# Analog_Interfaces.net
KiCad netlist of a schematic drawn in Altium Designer
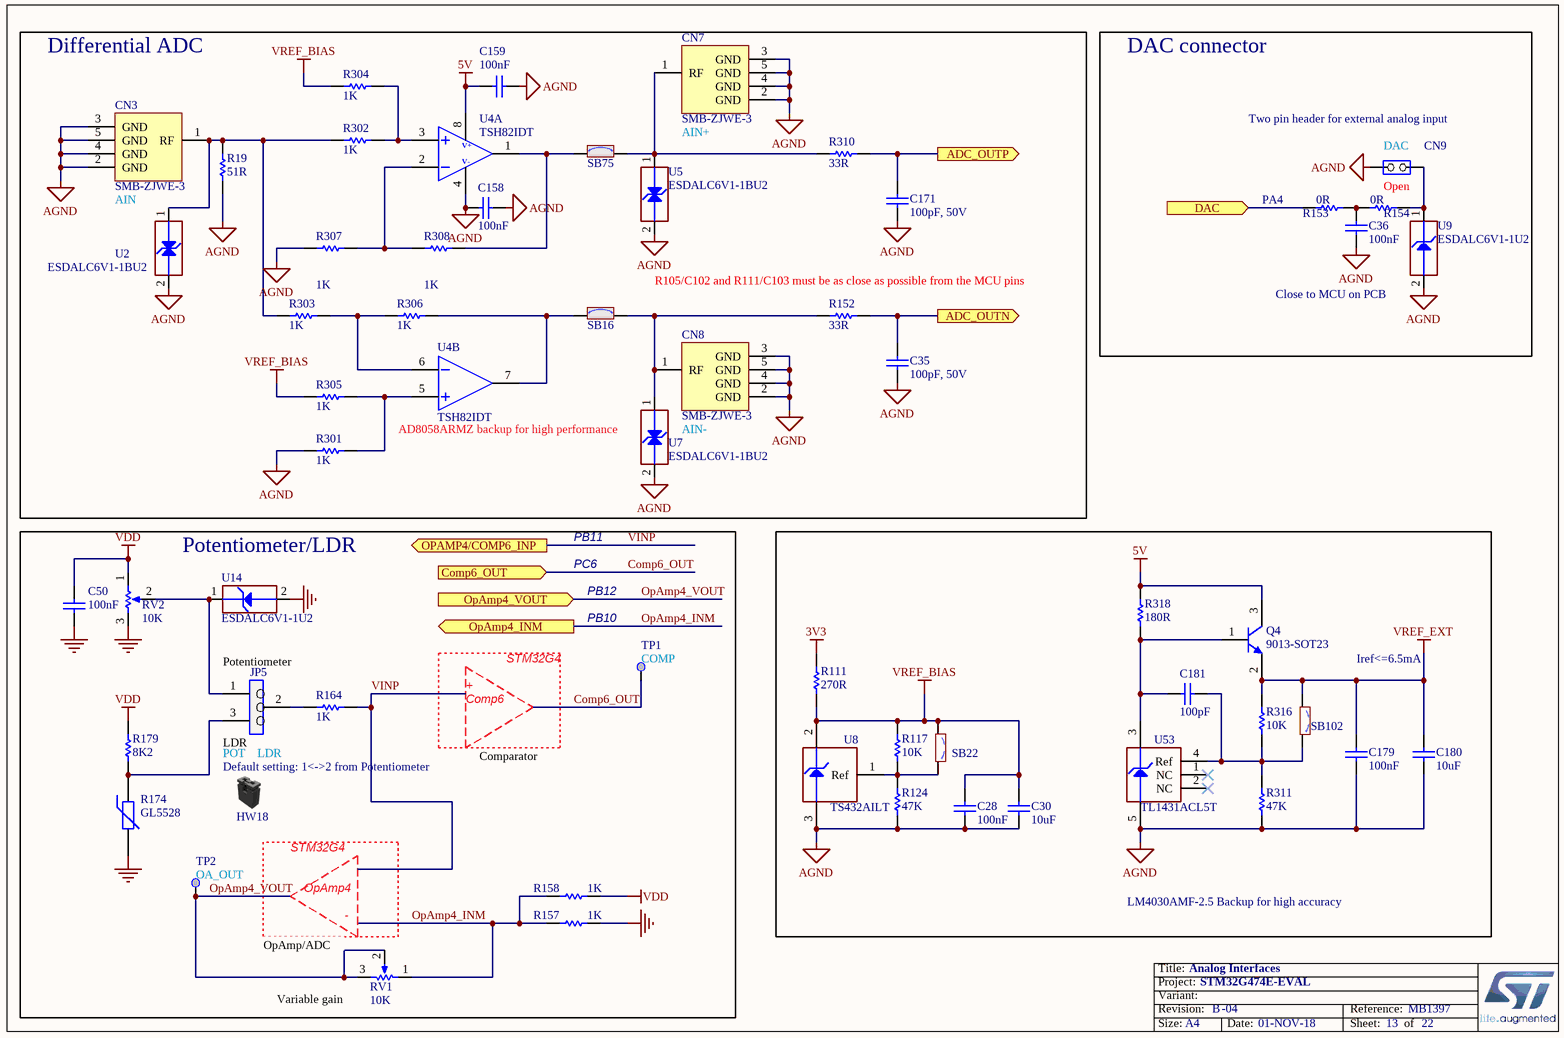
[diagram p0: Analog Interfaces.SchDoc]

(export (version "E")
  (design (tool "Eeschema 10.0.6"))
  (components
    (comp (ref "C28")
      (value "100nF")
      (footprint "C0603")
      (description "Capacitor, MLCC, 100nF, 16V, X7R, 10%, 0603, T=0,8mm")
      (fields
        (field (name "INTERNAL_PART_NUMBER") "MCD-00211")
        (field (name "MANUFACTURER_PART_NUMBER") "CC0603KRX7R7BB104")
        (field (name "PROVIDED_BY") "SUBCO")
      )
      (libsource (lib "MCD_PARTS_database") (part "Capacitor"))
    )
    (comp (ref "C30")
      (value "10uF")
      (footprint "C0603")
      (description "Capacitor, MLCC, 10µF, 10V, X5R, 10%, 0603, T=0.8mm")
      (fields
        (field (name "INTERNAL_PART_NUMBER") "MCD-01124")
        (field (name "MANUFACTURER_PART_NUMBER") "GRM188R61A106KAAL")
        (field (name "PROVIDED_BY") "SUBCO")
      )
      (libsource (lib "MCD_PARTS_database") (part "Capacitor"))
    )
    (comp (ref "C35")
      (value "100pF, 50V")
      (footprint "C0603")
      (description "Capacitor,100pF,50V,X7R,10%,0603")
      (fields
        (field (name "INTERNAL_PART_NUMBER") "MCD-01101")
        (field (name "MANUFACTURER_PART_NUMBER") "06035C101JAT4A")
        (field (name "PROVIDED_BY") "SUBCO")
      )
      (libsource (lib "MCD_PARTS_database") (part "Capacitor"))
    )
    (comp (ref "C36")
      (value "100nF")
      (footprint "C0603")
      (description "Capacitor, MLCC, 100nF, 16V, X7R, 10%, 0603, T=0,8mm")
      (fields
        (field (name "INTERNAL_PART_NUMBER") "MCD-00211")
        (field (name "MANUFACTURER_PART_NUMBER") "CC0603KRX7R7BB104")
        (field (name "PROVIDED_BY") "SUBCO")
      )
      (libsource (lib "MCD_PARTS_database") (part "Capacitor"))
    )
    (comp (ref "C50")
      (value "100nF")
      (footprint "C0402")
      (description "Capacitor, MLCC, 100nF, 16V, X7R, 10%, 0402, T=0.5mm")
      (fields
        (field (name "INTERNAL_PART_NUMBER") "MCD-00006")
        (field (name "MANUFACTURER_PART_NUMBER") "CC0402KRX7R7BB104")
        (field (name "PROVIDED_BY") "SUBCO")
      )
      (libsource (lib "MCD_PARTS_database") (part "Capacitor"))
    )
    (comp (ref "C158")
      (value "100nF")
      (footprint "C0603")
      (description "Capacitor, MLCC, 100nF, 16V, X7R, 10%, 0603, T=0,8mm")
      (fields
        (field (name "INTERNAL_PART_NUMBER") "MCD-00211")
        (field (name "MANUFACTURER_PART_NUMBER") "CC0603KRX7R7BB104")
        (field (name "PROVIDED_BY") "SUBCO")
      )
      (libsource (lib "MCD_PARTS_database") (part "Capacitor"))
    )
    (comp (ref "C159")
      (value "100nF")
      (footprint "C0603")
      (description "Capacitor, MLCC, 100nF, 16V, X7R, 10%, 0603, T=0,8mm")
      (fields
        (field (name "INTERNAL_PART_NUMBER") "MCD-00211")
        (field (name "MANUFACTURER_PART_NUMBER") "CC0603KRX7R7BB104")
        (field (name "PROVIDED_BY") "SUBCO")
      )
      (libsource (lib "MCD_PARTS_database") (part "Capacitor"))
    )
    (comp (ref "C171")
      (value "100pF, 50V")
      (footprint "C0603")
      (description "Capacitor,100pF,50V,X7R,10%,0603")
      (fields
        (field (name "INTERNAL_PART_NUMBER") "MCD-01101")
        (field (name "MANUFACTURER_PART_NUMBER") "06035C101JAT4A")
        (field (name "PROVIDED_BY") "SUBCO")
      )
      (libsource (lib "MCD_PARTS_database") (part "Capacitor"))
    )
    (comp (ref "C179")
      (value "100nF")
      (footprint "C0603")
      (description "Capacitor, MLCC, 100nF, 16V, X7R, 10%, 0603, T=0,8mm")
      (fields
        (field (name "INTERNAL_PART_NUMBER") "MCD-00211")
        (field (name "MANUFACTURER_PART_NUMBER") "CC0603KRX7R7BB104")
        (field (name "PROVIDED_BY") "SUBCO")
      )
      (libsource (lib "MCD_PARTS_database") (part "Capacitor"))
    )
    (comp (ref "C180")
      (value "10uF")
      (footprint "C0603")
      (description "Capacitor, MLCC, 10µF, 10V, X5R, 10%, 0603, T=0.8mm")
      (fields
        (field (name "INTERNAL_PART_NUMBER") "MCD-01124")
        (field (name "MANUFACTURER_PART_NUMBER") "GRM188R61A106KAAL")
        (field (name "PROVIDED_BY") "SUBCO")
      )
      (libsource (lib "MCD_PARTS_database") (part "Capacitor"))
    )
    (comp (ref "C181")
      (value "100pF")
      (footprint "C0402")
      (description "Capacitor, MLCC, 100pF, 50V, NPO, 5%, 0402, T=0,5mm")
      (fields
        (field (name "INTERNAL_PART_NUMBER") "MCD-00205")
        (field (name "MANUFACTURER_PART_NUMBER") "CC0402JRNPO9BN101")
        (field (name "PROVIDED_BY") "SUBCO")
      )
      (libsource (lib "MCD_PARTS_database") (part "Capacitor"))
    )
    (comp (ref "CN3")
      (value "SMB-ZJWE-3")
      (footprint "CON_JACK-RIGHT-ANGLE_YJ-ELECTRONIC_SMB-ZJWE-3")
      (description "SMB type right angle jack for PCB")
      (fields
        (field (name "INTERNAL_PART_NUMBER") "MCD-01181")
        (field (name "MANUFACTURER") "Yangzhou JingCheng Electronic Co., LTD")
        (field (name "PROVIDED_BY") "SUBCO")
      )
      (libsource (lib "MCD_PARTS_database") (part "SMB-ZJWE-3"))
    )
    (comp (ref "CN7")
      (value "SMB-ZJWE-3")
      (footprint "CON_JACK-RIGHT-ANGLE_YJ-ELECTRONIC_SMB-ZJWE-3")
      (description "SMB type right angle jack for PCB")
      (fields
        (field (name "INTERNAL_PART_NUMBER") "MCD-01181")
        (field (name "MANUFACTURER") "Yangzhou JingCheng Electronic Co., LTD")
        (field (name "PROVIDED_BY") "SUBCO")
      )
      (libsource (lib "") (part "SMB-ZJWE-3_1"))
    )
    (comp (ref "CN8")
      (value "SMB-ZJWE-3")
      (footprint "CON_JACK-RIGHT-ANGLE_YJ-ELECTRONIC_SMB-ZJWE-3")
      (description "SMB type right angle jack for PCB")
      (fields
        (field (name "INTERNAL_PART_NUMBER") "MCD-01181")
        (field (name "MANUFACTURER") "Yangzhou JingCheng Electronic Co., LTD")
        (field (name "PROVIDED_BY") "SUBCO")
      )
      (libsource (lib "") (part "SMB-ZJWE-3_1"))
    )
    (comp (ref "CN9")
      (value "Jumper_Header 2x1")
      (footprint "CON_SAMTEC_TSW-102-07-G-S")
      (description "Header, 2x1, 2,54mm, VR, TH, Height 5.84mm/2.54mm")
      (fields
        (field (name "INTERNAL_PART_NUMBER") "MCD-00045")
        (field (name "MANUFACTURER_PART_NUMBER") "TSW-102-07-x-S")
        (field (name "PROVIDED_BY") "SUBCO")
      )
      (libsource (lib "MCD_PARTS_database") (part "Jumper_Header 2x1"))
    )
    (comp (ref "HW18")
      (value "Shunt Black 2.54mm")
      (description "SHUNT 2.54mm BLACK")
      (fields
        (field (name "INTERNAL_PART_NUMBER") "MCD-00043")
        (field (name "MANUFACTURER_PART_NUMBER") "SNT-100-BK-G")
        (field (name "PROVIDED_BY") "SUBCO")
      )
      (libsource (lib "MCD_PARTS_database") (part "Shunt Black 2.54mm"))
    )
    (comp (ref "JP5")
      (value "Jumper_Header 3x1")
      (footprint "CON_SAMTEC_TSW-103-07-F-S")
      (description "Header, 3x1, 2,54mm, VR, TH, Height 5.84mm/2.54mm")
      (fields
        (field (name "INTERNAL_PART_NUMBER") "MCD-00111")
        (field (name "MANUFACTURER_PART_NUMBER") "TSW-103-07-F-S")
        (field (name "PROVIDED_BY") "SUBCO")
      )
      (libsource (lib "MCD_PARTS_database") (part "Jumper_Header 3x1"))
    )
    (comp (ref "Q4")
      (value "9013-SOT23")
      (footprint "NPN_SOT23")
      (description "NPN Bipolar Transistor")
      (fields
        (field (name "INTERNAL_PART_NUMBER") "MCD-00073")
        (field (name "MANUFACTURER_PART_NUMBER") "BSR14")
        (field (name "PROVIDED_BY") "SUBCO")
      )
      (libsource (lib "MCD_PARTS_database") (part "9013-SOT23"))
    )
    (comp (ref "R19")
      (value "51R")
      (footprint "R0603")
      (description "Resistor,51R,0603,1%,1/10W")
      (fields
        (field (name "INTERNAL_PART_NUMBER") "MCD-00486")
        (field (name "MANUFACTURER_PART_NUMBER") "RC0603FR-0751RL")
        (field (name "PROVIDED_BY") "SUBCO")
      )
      (libsource (lib "MCD_PARTS_database") (part "Resistor"))
    )
    (comp (ref "R111")
      (value "270R")
      (footprint "R0603")
      (description "Resistor,270R,0603,1%,1/10W")
      (fields
        (field (name "INTERNAL_PART_NUMBER") "MCD-00442")
        (field (name "MANUFACTURER_PART_NUMBER") "RC0603FR-07270RL")
        (field (name "PROVIDED_BY") "SUBCO")
      )
      (libsource (lib "MCD_PARTS_database") (part "Resistor"))
    )
    (comp (ref "R117")
      (value "10K")
      (footprint "R0603")
      (description "Resistor,10K,0603,1%,1/10W")
      (fields
        (field (name "INTERNAL_PART_NUMBER") "MCD-00220")
        (field (name "MANUFACTURER_PART_NUMBER") "RC0603FR-0710KL")
        (field (name "PROVIDED_BY") "SUBCO")
      )
      (libsource (lib "MCD_PARTS_database") (part "Resistor"))
    )
    (comp (ref "R124")
      (value "47K")
      (footprint "R0603")
      (description "Resistor,47K,0603,1%,1/10W")
      (fields
        (field (name "INTERNAL_PART_NUMBER") "MCD-00222")
        (field (name "MANUFACTURER_PART_NUMBER") "RC0603FR-0747KL")
        (field (name "PROVIDED_BY") "SUBCO")
      )
      (libsource (lib "MCD_PARTS_database") (part "Resistor"))
    )
    (comp (ref "R152")
      (value "33R")
      (footprint "R0603")
      (description "Resistor,33R,0603,1%,1/10W")
      (fields
        (field (name "INTERNAL_PART_NUMBER") "MCD-00456")
        (field (name "MANUFACTURER_PART_NUMBER") "RC0603FR-0733RL")
        (field (name "PROVIDED_BY") "SUBCO")
      )
      (libsource (lib "MCD_PARTS_database") (part "Resistor"))
    )
    (comp (ref "R153")
      (value "0R")
      (footprint "R0603")
      (description "Resistor,0R,0603,5%,1/10W")
      (fields
        (field (name "INTERNAL_PART_NUMBER") "MCD-00056")
        (field (name "MANUFACTURER_PART_NUMBER") "RC0603JR-070RL")
        (field (name "PROVIDED_BY") "SUBCO")
      )
      (libsource (lib "MCD_PARTS_database") (part "Resistor"))
    )
    (comp (ref "R154")
      (value "0R")
      (footprint "R0603")
      (description "Resistor,0R,0603,5%,1/10W")
      (fields
        (field (name "INTERNAL_PART_NUMBER") "MCD-00056")
        (field (name "MANUFACTURER_PART_NUMBER") "RC0603JR-070RL")
        (field (name "PROVIDED_BY") "SUBCO")
      )
      (libsource (lib "MCD_PARTS_database") (part "Resistor"))
    )
    (comp (ref "R157")
      (value "1K")
      (footprint "R0603")
      (description "Resistor,1K,0603,1%,1/10W")
      (fields
        (field (name "INTERNAL_PART_NUMBER") "MCD-00070")
        (field (name "MANUFACTURER_PART_NUMBER") "RC0603FR-071KL")
        (field (name "PROVIDED_BY") "SUBCO")
      )
      (libsource (lib "MCD_PARTS_database") (part "Resistor"))
    )
    (comp (ref "R158")
      (value "1K")
      (footprint "R0603")
      (description "Resistor,1K,0603,1%,1/10W")
      (fields
        (field (name "INTERNAL_PART_NUMBER") "MCD-00070")
        (field (name "MANUFACTURER_PART_NUMBER") "RC0603FR-071KL")
        (field (name "PROVIDED_BY") "SUBCO")
      )
      (libsource (lib "MCD_PARTS_database") (part "Resistor"))
    )
    (comp (ref "R164")
      (value "1K")
      (footprint "R0603")
      (description "Resistor,1K,0603,1%,1/10W")
      (fields
        (field (name "INTERNAL_PART_NUMBER") "MCD-00070")
        (field (name "MANUFACTURER_PART_NUMBER") "RC0603FR-071KL")
        (field (name "PROVIDED_BY") "SUBCO")
      )
      (libsource (lib "MCD_PARTS_database") (part "Resistor"))
    )
    (comp (ref "R174")
      (value "GL5528")
      (footprint "PHO_SENBAN_GL55XX")
      (description "GL55 series  photoconductive cell: Light resistance 10Lux range 10-20KOhm, Dark 1MOhm")
      (fields
        (field (name "INTERNAL_PART_NUMBER") "MCD-01158")
        (field (name "MANUFACTURER") "SHENZHEN SENBAN OPTICAL & ELECTRONIC CO. LTD")
        (field (name "PROVIDED_BY") "SUBCO")
      )
      (libsource (lib "MCD_PARTS_database") (part "PT100"))
    )
    (comp (ref "R179")
      (value "8K2")
      (footprint "R0603")
      (description "Resistor,8K2,0603,1%,1/10W")
      (fields
        (field (name "INTERNAL_PART_NUMBER") "MCD-00530")
        (field (name "MANUFACTURER_PART_NUMBER") "RC0603FR-078K2L")
        (field (name "PROVIDED_BY") "SUBCO")
      )
      (libsource (lib "MCD_PARTS_database") (part "Resistor"))
    )
    (comp (ref "R301")
      (value "1K")
      (footprint "R0603")
      (description "Resistor,1K,0603,1%,1/10W")
      (fields
        (field (name "INTERNAL_PART_NUMBER") "MCD-00070")
        (field (name "MANUFACTURER_PART_NUMBER") "RC0603FR-071KL")
        (field (name "PROVIDED_BY") "SUBCO")
      )
      (libsource (lib "MCD_PARTS_database") (part "Resistor"))
    )
    (comp (ref "R302")
      (value "1K")
      (footprint "R0603")
      (description "Resistor,1K,0603,1%,1/10W")
      (fields
        (field (name "INTERNAL_PART_NUMBER") "MCD-00070")
        (field (name "MANUFACTURER_PART_NUMBER") "RC0603FR-071KL")
        (field (name "PROVIDED_BY") "SUBCO")
      )
      (libsource (lib "MCD_PARTS_database") (part "Resistor"))
    )
    (comp (ref "R303")
      (value "1K")
      (footprint "R0603")
      (description "Resistor,1K,0603,1%,1/10W")
      (fields
        (field (name "INTERNAL_PART_NUMBER") "MCD-00070")
        (field (name "MANUFACTURER_PART_NUMBER") "RC0603FR-071KL")
        (field (name "PROVIDED_BY") "SUBCO")
      )
      (libsource (lib "MCD_PARTS_database") (part "Resistor"))
    )
    (comp (ref "R304")
      (value "1K")
      (footprint "R0603")
      (description "Resistor,1K,0603,1%,1/10W")
      (fields
        (field (name "INTERNAL_PART_NUMBER") "MCD-00070")
        (field (name "MANUFACTURER_PART_NUMBER") "RC0603FR-071KL")
        (field (name "PROVIDED_BY") "SUBCO")
      )
      (libsource (lib "MCD_PARTS_database") (part "Resistor"))
    )
    (comp (ref "R305")
      (value "1K")
      (footprint "R0603")
      (description "Resistor,1K,0603,1%,1/10W")
      (fields
        (field (name "INTERNAL_PART_NUMBER") "MCD-00070")
        (field (name "MANUFACTURER_PART_NUMBER") "RC0603FR-071KL")
        (field (name "PROVIDED_BY") "SUBCO")
      )
      (libsource (lib "MCD_PARTS_database") (part "Resistor"))
    )
    (comp (ref "R306")
      (value "1K")
      (footprint "R0603")
      (description "Resistor,1K,0603,1%,1/10W")
      (fields
        (field (name "INTERNAL_PART_NUMBER") "MCD-00070")
        (field (name "MANUFACTURER_PART_NUMBER") "RC0603FR-071KL")
        (field (name "PROVIDED_BY") "SUBCO")
      )
      (libsource (lib "MCD_PARTS_database") (part "Resistor"))
    )
    (comp (ref "R307")
      (value "1K")
      (footprint "R0603")
      (description "Resistor,1K,0603,1%,1/10W")
      (fields
        (field (name "INTERNAL_PART_NUMBER") "MCD-00070")
        (field (name "MANUFACTURER_PART_NUMBER") "RC0603FR-071KL")
        (field (name "PROVIDED_BY") "SUBCO")
      )
      (libsource (lib "MCD_PARTS_database") (part "Resistor"))
    )
    (comp (ref "R308")
      (value "1K")
      (footprint "R0603")
      (description "Resistor,1K,0603,1%,1/10W")
      (fields
        (field (name "INTERNAL_PART_NUMBER") "MCD-00070")
        (field (name "MANUFACTURER_PART_NUMBER") "RC0603FR-071KL")
        (field (name "PROVIDED_BY") "SUBCO")
      )
      (libsource (lib "MCD_PARTS_database") (part "Resistor"))
    )
    (comp (ref "R310")
      (value "33R")
      (footprint "R0603")
      (description "Resistor,33R,0603,1%,1/10W")
      (fields
        (field (name "INTERNAL_PART_NUMBER") "MCD-00456")
        (field (name "MANUFACTURER_PART_NUMBER") "RC0603FR-0733RL")
        (field (name "PROVIDED_BY") "SUBCO")
      )
      (libsource (lib "MCD_PARTS_database") (part "Resistor"))
    )
    (comp (ref "R311")
      (value "47K")
      (footprint "R0603")
      (description "Resistor,47K,0603,1%,1/10W")
      (fields
        (field (name "INTERNAL_PART_NUMBER") "MCD-00222")
        (field (name "MANUFACTURER_PART_NUMBER") "RC0603FR-0747KL")
        (field (name "PROVIDED_BY") "SUBCO")
      )
      (libsource (lib "MCD_PARTS_database") (part "Resistor"))
    )
    (comp (ref "R316")
      (value "10K")
      (footprint "R0603")
      (description "Resistor,10K,0603,1%,1/10W")
      (fields
        (field (name "INTERNAL_PART_NUMBER") "MCD-00220")
        (field (name "MANUFACTURER_PART_NUMBER") "RC0603FR-0710KL")
        (field (name "PROVIDED_BY") "SUBCO")
      )
      (libsource (lib "MCD_PARTS_database") (part "Resistor"))
    )
    (comp (ref "R318")
      (value "180R")
      (footprint "R0603")
      (description "Resistor,180R,0603,1%,1/10W")
      (fields
        (field (name "INTERNAL_PART_NUMBER") "MCD-00342")
        (field (name "MANUFACTURER_PART_NUMBER") "RC0603FR-07180RL")
        (field (name "PROVIDED_BY") "SUBCO")
      )
      (libsource (lib "MCD_PARTS_database") (part "Resistor"))
    )
    (comp (ref "RV1")
      (value "10K")
      (footprint "POT_BOURNS_3314J-1")
      (description "4mm Square Trimming Potentiometer 10K OHM 0.25W PC PIN")
      (fields
        (field (name "INTERNAL_PART_NUMBER") "MCD-01169")
        (field (name "MANUFACTURER_PART_NUMBER") "3314J-1-103")
        (field (name "PROVIDED_BY") "SUBCO")
      )
      (libsource (lib "MCD_PARTS_database") (part "POTENTIOMETER"))
    )
    (comp (ref "RV2")
      (value "10K")
      (footprint "POT_BOURNS_3386P")
      (description "TRIMMER 10K OHM 0.5W PC PIN")
      (fields
        (field (name "INTERNAL_PART_NUMBER") "MCD-00575")
        (field (name "MANUFACTURER_PART_NUMBER") "3386P-1-103")
        (field (name "PROVIDED_BY") "SUBCO")
      )
      (libsource (lib "MCD_PARTS_database") (part "POTENTIOMETER"))
    )
    (comp (ref "SB16")
      (value "SB_ON")
      (footprint "SOLDER-BRIDGE_R0603-0R")
      (description "Solder Bridge ON")
      (fields
        (field (name "INTERNAL_PART_NUMBER") "MCD-00071")
        (field (name "MANUFACTURER_PART_NUMBER") "RC0603JR-070RL")
        (field (name "PROVIDED_BY") "SUBCO")
      )
      (libsource (lib "MCD_PARTS_database") (part "SB_ON"))
    )
    (comp (ref "SB22")
      (value "SB_OFF")
      (footprint "SOLDER-BRIDGE_R0603-0R")
      (description "Solder Bridge OFF")
      (fields
        (field (name "INTERNAL_PART_NUMBER") "MCD-00072")
        (field (name "MANUFACTURER_PART_NUMBER") "RC0603JR-070RL")
        (field (name "PROVIDED_BY") "SUBCO")
      )
      (libsource (lib "MCD_PARTS_database") (part "SB_OFF"))
    )
    (comp (ref "SB75")
      (value "SB_ON")
      (footprint "SOLDER-BRIDGE_R0603-0R")
      (description "Solder Bridge ON")
      (fields
        (field (name "INTERNAL_PART_NUMBER") "MCD-00071")
        (field (name "MANUFACTURER_PART_NUMBER") "RC0603JR-070RL")
        (field (name "PROVIDED_BY") "SUBCO")
      )
      (libsource (lib "MCD_PARTS_database") (part "SB_ON"))
    )
    (comp (ref "SB102")
      (value "SB_OFF")
      (footprint "SOLDER-BRIDGE_R0603-0R")
      (description "Solder Bridge OFF")
      (fields
        (field (name "INTERNAL_PART_NUMBER") "MCD-00072")
        (field (name "MANUFACTURER_PART_NUMBER") "RC0603JR-070RL")
        (field (name "PROVIDED_BY") "SUBCO")
      )
      (libsource (lib "MCD_PARTS_database") (part "SB_OFF"))
    )
    (comp (ref "TP1")
      (value "Test Point")
      (footprint "TP_SMD_1MM")
      (description "Test Point 1mm")
      (fields (field (name "INTERNAL_PART_NUMBER") "MCD-00074") (field (name "MANUFACTURER") "n/a"))
      (libsource (lib "MCD_PARTS_database") (part "Test Point"))
    )
    (comp (ref "TP2")
      (value "Test Point")
      (footprint "TP_SMD_1MM")
      (description "Test Point 1mm")
      (fields (field (name "INTERNAL_PART_NUMBER") "MCD-00074") (field (name "MANUFACTURER") "n/a"))
      (libsource (lib "MCD_PARTS_database") (part "Test Point"))
    )
    (comp (ref "U2")
      (value "ESDALC6V1-1BU2")
      (footprint "ESD_ST0201")
      (description "Single-line low capacitance Transil for bidirectional ESD protection 6V1")
      (fields
        (field (name "INTERNAL_PART_NUMBER") "MCD-01242")
        (field (name "MANUFACTURER") "STMICROELECTRONICS")
        (field (name "PROVIDED_BY") "SUBCO with ST control")
      )
      (libsource (lib "MCD_PARTS_database") (part "ESD-TRANSIL-BIDIR"))
    )
    (comp (ref "U4")
      (value "TSH82IDT")
      (footprint "ICC_SO8_5X4_P127")
      (description "Wide-band Rail-to-Rail operational amplifiers with standby function")
      (fields
        (field (name "INTERNAL_PART_NUMBER") "MCD-01205")
        (field (name "MANUFACTURER") "STMICROELECTRONICS")
        (field (name "PROVIDED_BY") "SUBCO with ST control")
      )
      (libsource (lib "MCD_PARTS_database") (part "TSH82IDT"))
    )
    (comp (ref "U5")
      (value "ESDALC6V1-1BU2")
      (footprint "ESD_ST0201")
      (description "Single-line low capacitance Transil for bidirectional ESD protection 6V1")
      (fields
        (field (name "INTERNAL_PART_NUMBER") "MCD-01242")
        (field (name "MANUFACTURER") "STMICROELECTRONICS")
        (field (name "PROVIDED_BY") "SUBCO with ST control")
      )
      (libsource (lib "MCD_PARTS_database") (part "ESD-TRANSIL-BIDIR"))
    )
    (comp (ref "U7")
      (value "ESDALC6V1-1BU2")
      (footprint "ESD_ST0201")
      (description "Single-line low capacitance Transil for bidirectional ESD protection 6V1")
      (fields
        (field (name "INTERNAL_PART_NUMBER") "MCD-01242")
        (field (name "MANUFACTURER") "STMICROELECTRONICS")
        (field (name "PROVIDED_BY") "SUBCO with ST control")
      )
      (libsource (lib "MCD_PARTS_database") (part "ESD-TRANSIL-BIDIR"))
    )
    (comp (ref "U8")
      (value "TS432AILT")
      (footprint "ICC_SOT23-3L_H1P12")
      (description "1.24V adjustable shunt voltage reference, Precision 0.5%")
      (fields
        (field (name "INTERNAL_PART_NUMBER") "MCD-01204")
        (field (name "MANUFACTURER") "STMICROELECTRONICS")
        (field (name "PROVIDED_BY") "SUBCO with ST control")
      )
      (libsource (lib "MCD_PARTS_database") (part "TS432AILT"))
    )
    (comp (ref "U9")
      (value "ESDALC6V1-1U2")
      (footprint "ESD_ST0201")
      (description "ESD protection 6V1")
      (fields
        (field (name "INTERNAL_PART_NUMBER") "MCD-00170")
        (field (name "MANUFACTURER") "STMICROELECTRONICS")
        (field (name "PROVIDED_BY") "SUBCO with ST control")
      )
      (libsource (lib "") (part "ESD-TRANSIL_1"))
    )
    (comp (ref "U14")
      (value "ESDALC6V1-1U2")
      (footprint "ESD_ST0201")
      (description "ESD protection 6V1")
      (fields
        (field (name "INTERNAL_PART_NUMBER") "MCD-00170")
        (field (name "MANUFACTURER") "STMICROELECTRONICS")
        (field (name "PROVIDED_BY") "SUBCO with ST control")
      )
      (libsource (lib "MCD_PARTS_database") (part "ESD-TRANSIL"))
    )
    (comp (ref "U53")
      (value "TL1431ACL5T")
      (footprint "ICC_SOT23-5L_H1P45")
      (description "Programmable voltage reference")
      (fields
        (field (name "INTERNAL_PART_NUMBER") "MCD-01157")
        (field (name "MANUFACTURER") "STMICROELECTRONICS")
        (field (name "PROVIDED_BY") "SUBCO with ST control")
      )
      (libsource (lib "MCD_PARTS_database") (part "TL1431ACL5T"))
    )
  )
  (nets
    (net (code "1") (name "/ADC_OUTN") (class "Default")
      (node (ref "C35") (pin "1") (pinfunction "1_1") (pintype "passive"))
      (node (ref "R152") (pin "2") (pinfunction "2_2") (pintype "passive"))
    )
    (net (code "2") (name "/ADC_OUTP") (class "Default")
      (node (ref "C171") (pin "2") (pinfunction "2_2") (pintype "passive"))
      (node (ref "R310") (pin "2") (pinfunction "2_2") (pintype "passive"))
    )
    (net (code "3") (name "/Comp6_OUT") (class "Default")
      (node (ref "TP1") (pin "1") (pinfunction "1_1") (pintype "passive"))
    )
    (net (code "4") (name "/DAC") (class "Default")
      (node (ref "R153") (pin "2") (pinfunction "2_2") (pintype "passive"))
    )
    (net (code "5") (name "/OpAmp4_INM") (class "Default")
      (node (ref "R157") (pin "1") (pinfunction "1_1") (pintype "passive"))
      (node (ref "R158") (pin "1") (pinfunction "1_1") (pintype "passive"))
      (node (ref "RV1") (pin "1") (pinfunction "BOT_1") (pintype "passive"))
    )
    (net (code "6") (name "/OpAmp4_VOUT") (class "Default")
      (node (ref "RV1") (pin "2") (pinfunction "TAP_2") (pintype "passive"))
      (node (ref "RV1") (pin "3") (pinfunction "TOP_3") (pintype "passive"))
      (node (ref "TP2") (pin "1") (pinfunction "1_1") (pintype "passive"))
    )
    (net (code "7") (name "/VINP") (class "Default")
      (node (ref "R164") (pin "1") (pinfunction "1_1") (pintype "passive"))
    )
    (net (code "8") (name "3V3") (class "Default")
      (node (ref "R111") (pin "2") (pinfunction "2_2") (pintype "passive"))
    )
    (net (code "9") (name "5V") (class "Default")
      (node (ref "C159") (pin "2") (pinfunction "2_2") (pintype "passive"))
      (node (ref "Q4") (pin "3") (pinfunction "C_3") (pintype "passive"))
      (node (ref "R318") (pin "2") (pinfunction "2_2") (pintype "passive"))
      (node (ref "U4") (pin "8") (pintype "passive"))
    )
    (net (code "10") (name "AGND") (class "Default")
      (node (ref "C158") (pin "1") (pinfunction "1_1") (pintype "passive"))
      (node (ref "C158") (pin "2") (pinfunction "2_2") (pintype "passive"))
      (node (ref "C159") (pin "1") (pinfunction "1_1") (pintype "passive"))
      (node (ref "C171") (pin "1") (pinfunction "1_1") (pintype "passive"))
      (node (ref "C179") (pin "1") (pinfunction "1_1") (pintype "passive"))
      (node (ref "C180") (pin "1") (pinfunction "1_1") (pintype "passive"))
      (node (ref "C28") (pin "1") (pinfunction "1_1") (pintype "passive"))
      (node (ref "C30") (pin "1") (pinfunction "1_1") (pintype "passive"))
      (node (ref "C35") (pin "2") (pinfunction "2_2") (pintype "passive"))
      (node (ref "C36") (pin "2") (pinfunction "2_2") (pintype "passive"))
      (node (ref "CN3") (pin "2") (pinfunction "GND_2") (pintype "passive"))
      (node (ref "CN3") (pin "3") (pinfunction "GND_3") (pintype "passive"))
      (node (ref "CN3") (pin "4") (pinfunction "GND_4") (pintype "passive"))
      (node (ref "CN3") (pin "5") (pinfunction "GND_5") (pintype "passive"))
      (node (ref "CN7") (pin "2") (pinfunction "GND_2") (pintype "passive"))
      (node (ref "CN7") (pin "3") (pinfunction "GND_3") (pintype "passive"))
      (node (ref "CN7") (pin "4") (pinfunction "GND_4") (pintype "passive"))
      (node (ref "CN7") (pin "5") (pinfunction "GND_5") (pintype "passive"))
      (node (ref "CN8") (pin "2") (pinfunction "GND_2") (pintype "passive"))
      (node (ref "CN8") (pin "3") (pinfunction "GND_3") (pintype "passive"))
      (node (ref "CN8") (pin "4") (pinfunction "GND_4") (pintype "passive"))
      (node (ref "CN8") (pin "5") (pinfunction "GND_5") (pintype "passive"))
      (node (ref "CN9") (pin "2") (pinfunction "NO_2") (pintype "passive"))
      (node (ref "R124") (pin "1") (pinfunction "1_1") (pintype "passive"))
      (node (ref "R19") (pin "1") (pinfunction "1_1") (pintype "passive"))
      (node (ref "R301") (pin "2") (pinfunction "2_2") (pintype "passive"))
      (node (ref "R307") (pin "2") (pinfunction "2_2") (pintype "passive"))
      (node (ref "R311") (pin "1") (pinfunction "1_1") (pintype "passive"))
      (node (ref "U2") (pin "2") (pinfunction "GND_2") (pintype "passive"))
      (node (ref "U4") (pin "4") (pintype "passive"))
      (node (ref "U5") (pin "2") (pinfunction "GND_2") (pintype "passive"))
      (node (ref "U53") (pin "5") (pinfunction "Anode_5") (pintype "passive"))
      (node (ref "U7") (pin "2") (pinfunction "GND_2") (pintype "passive"))
      (node (ref "U8") (pin "3") (pinfunction "Anode_3") (pintype "passive"))
      (node (ref "U9") (pin "2") (pinfunction "GND_2") (pintype "passive"))
    )
    (net (code "11") (name "GND") (class "Default")
      (node (ref "C50") (pin "2") (pinfunction "2_2") (pintype "passive"))
      (node (ref "R157") (pin "2") (pinfunction "2_2") (pintype "passive"))
      (node (ref "R174") (pin "2") (pinfunction "2_2") (pintype "passive"))
      (node (ref "RV2") (pin "3") (pinfunction "TOP_3") (pintype "passive"))
      (node (ref "U14") (pin "2") (pinfunction "GND_2") (pintype "passive"))
    )
    (net (code "12") (name "Net-(C36-Pad1)") (class "Default")
      (node (ref "C36") (pin "1") (pinfunction "1_1") (pintype "passive"))
      (node (ref "R153") (pin "1") (pinfunction "1_1") (pintype "passive"))
      (node (ref "R154") (pin "1") (pinfunction "1_1") (pintype "passive"))
    )
    (net (code "13") (name "Net-(CN3-RF)") (class "Default")
      (node (ref "CN3") (pin "1") (pinfunction "RF_1") (pintype "passive"))
      (node (ref "R19") (pin "2") (pinfunction "2_2") (pintype "passive"))
      (node (ref "R302") (pin "1") (pinfunction "1_1") (pintype "passive"))
      (node (ref "R303") (pin "2") (pinfunction "2_2") (pintype "passive"))
      (node (ref "U2") (pin "1") (pinfunction "IO1_1") (pintype "passive"))
    )
    (net (code "14") (name "Net-(CN7-RF)") (class "Default")
      (node (ref "CN7") (pin "1") (pinfunction "RF_1") (pintype "passive"))
      (node (ref "R310") (pin "1") (pinfunction "1_1") (pintype "passive"))
      (node (ref "SB75") (pin "2") (pinfunction "2_2") (pintype "passive"))
      (node (ref "U5") (pin "1") (pinfunction "IO1_1") (pintype "passive"))
    )
    (net (code "15") (name "Net-(CN8-RF)") (class "Default")
      (node (ref "CN8") (pin "1") (pinfunction "RF_1") (pintype "passive"))
      (node (ref "R152") (pin "1") (pinfunction "1_1") (pintype "passive"))
      (node (ref "SB16") (pin "2") (pinfunction "2_2") (pintype "passive"))
      (node (ref "U7") (pin "1") (pinfunction "IO1_1") (pintype "passive"))
    )
    (net (code "16") (name "Net-(CN9-COMMON)") (class "Default")
      (node (ref "CN9") (pin "1") (pinfunction "COMMON_1") (pintype "passive"))
      (node (ref "R154") (pin "2") (pinfunction "2_2") (pintype "passive"))
      (node (ref "U9") (pin "1") (pinfunction "IO1_1") (pintype "passive"))
    )
    (net (code "17") (name "Net-(JP5-Pad2)") (class "Default")
      (node (ref "JP5") (pin "2") (pinfunction "2_2") (pintype "passive"))
      (node (ref "R164") (pin "2") (pinfunction "2_2") (pintype "passive"))
    )
    (net (code "18") (name "Net-(JP5-Pad3)") (class "Default")
      (node (ref "JP5") (pin "3") (pinfunction "3_3") (pintype "passive"))
      (node (ref "R174") (pin "1") (pinfunction "1_1") (pintype "passive"))
      (node (ref "R179") (pin "1") (pinfunction "1_1") (pintype "passive"))
    )
    (net (code "19") (name "Net-(Q4-B)") (class "Default")
      (node (ref "C181") (pin "2") (pinfunction "2_2") (pintype "passive"))
      (node (ref "Q4") (pin "1") (pinfunction "B_1") (pintype "passive"))
      (node (ref "R318") (pin "1") (pinfunction "1_1") (pintype "passive"))
      (node (ref "U53") (pin "3") (pinfunction "Cathode_3") (pintype "passive"))
    )
    (net (code "20") (name "Net-(R301-Pad1)") (class "Default")
      (node (ref "R301") (pin "1") (pinfunction "1_1") (pintype "passive"))
      (node (ref "R305") (pin "2") (pinfunction "2_2") (pintype "passive"))
      (node (ref "U4") (pin "5") (pintype "passive"))
    )
    (net (code "21") (name "Net-(R302-Pad2)") (class "Default")
      (node (ref "R302") (pin "2") (pinfunction "2_2") (pintype "passive"))
      (node (ref "R304") (pin "2") (pinfunction "2_2") (pintype "passive"))
      (node (ref "U4") (pin "3") (pintype "passive"))
    )
    (net (code "22") (name "Net-(R303-Pad1)") (class "Default")
      (node (ref "R303") (pin "1") (pinfunction "1_1") (pintype "passive"))
      (node (ref "R306") (pin "2") (pinfunction "2_2") (pintype "passive"))
      (node (ref "U4") (pin "6") (pintype "passive"))
    )
    (net (code "23") (name "Net-(R306-Pad1)") (class "Default")
      (node (ref "R306") (pin "1") (pinfunction "1_1") (pintype "passive"))
      (node (ref "SB16") (pin "1") (pinfunction "1_1") (pintype "passive"))
      (node (ref "U4") (pin "7") (pintype "passive"))
    )
    (net (code "24") (name "Net-(R307-Pad1)") (class "Default")
      (node (ref "R307") (pin "1") (pinfunction "1_1") (pintype "passive"))
      (node (ref "R308") (pin "2") (pinfunction "2_2") (pintype "passive"))
      (node (ref "U4") (pin "2") (pintype "passive"))
    )
    (net (code "25") (name "Net-(R308-Pad1)") (class "Default")
      (node (ref "R308") (pin "1") (pinfunction "1_1") (pintype "passive"))
      (node (ref "SB75") (pin "1") (pinfunction "1_1") (pintype "passive"))
      (node (ref "U4") (pin "1") (pintype "passive"))
    )
    (net (code "26") (name "Net-(RV2-TAP)") (class "Default")
      (node (ref "JP5") (pin "1") (pinfunction "1_1") (pintype "passive"))
      (node (ref "RV2") (pin "2") (pinfunction "TAP_2") (pintype "passive"))
      (node (ref "U14") (pin "1") (pinfunction "IO1_1") (pintype "passive"))
    )
    (net (code "27") (name "Net-(U8-Ref)") (class "Default")
      (node (ref "R117") (pin "1") (pinfunction "1_1") (pintype "passive"))
      (node (ref "R124") (pin "2") (pinfunction "2_2") (pintype "passive"))
      (node (ref "SB22") (pin "2") (pinfunction "2_2") (pintype "passive"))
      (node (ref "U8") (pin "1") (pinfunction "Ref_1") (pintype "passive"))
    )
    (net (code "28") (name "Net-(U53-Ref)") (class "Default")
      (node (ref "C181") (pin "1") (pinfunction "1_1") (pintype "passive"))
      (node (ref "R311") (pin "2") (pinfunction "2_2") (pintype "passive"))
      (node (ref "R316") (pin "1") (pinfunction "1_1") (pintype "passive"))
      (node (ref "SB102") (pin "2") (pinfunction "2_2") (pintype "passive"))
      (node (ref "U53") (pin "4") (pinfunction "Ref_4") (pintype "passive"))
    )
    (net (code "29") (name "VDD") (class "Default")
      (node (ref "C50") (pin "1") (pinfunction "1_1") (pintype "passive"))
      (node (ref "R158") (pin "2") (pinfunction "2_2") (pintype "passive"))
      (node (ref "R179") (pin "2") (pinfunction "2_2") (pintype "passive"))
      (node (ref "RV2") (pin "1") (pinfunction "BOT_1") (pintype "passive"))
    )
    (net (code "30") (name "VREF_BIAS") (class "Default")
      (node (ref "C28") (pin "2") (pinfunction "2_2") (pintype "passive"))
      (node (ref "C30") (pin "2") (pinfunction "2_2") (pintype "passive"))
      (node (ref "R111") (pin "1") (pinfunction "1_1") (pintype "passive"))
      (node (ref "R117") (pin "2") (pinfunction "2_2") (pintype "passive"))
      (node (ref "R304") (pin "1") (pinfunction "1_1") (pintype "passive"))
      (node (ref "R305") (pin "1") (pinfunction "1_1") (pintype "passive"))
      (node (ref "SB22") (pin "1") (pinfunction "1_1") (pintype "passive"))
      (node (ref "U8") (pin "2") (pinfunction "Cathode_2") (pintype "passive"))
    )
    (net (code "31") (name "VREF_EXT") (class "Default")
      (node (ref "C179") (pin "2") (pinfunction "2_2") (pintype "passive"))
      (node (ref "C180") (pin "2") (pinfunction "2_2") (pintype "passive"))
      (node (ref "Q4") (pin "2") (pinfunction "E_2") (pintype "passive"))
      (node (ref "R316") (pin "2") (pinfunction "2_2") (pintype "passive"))
      (node (ref "SB102") (pin "1") (pinfunction "1_1") (pintype "passive"))
    )
    (net (code "32") (name "unconnected-(U53-NC-Pad1)") (class "Default")
      (node (ref "U53") (pin "1") (pinfunction "NC_1") (pintype "passive+no_connect"))
    )
    (net (code "33") (name "unconnected-(U53-NC-Pad2)") (class "Default")
      (node (ref "U53") (pin "2") (pinfunction "NC_2") (pintype "passive+no_connect"))
    )
  )
)
